# SDRAM.net
KiCad netlist of a schematic drawn in Altium Designer
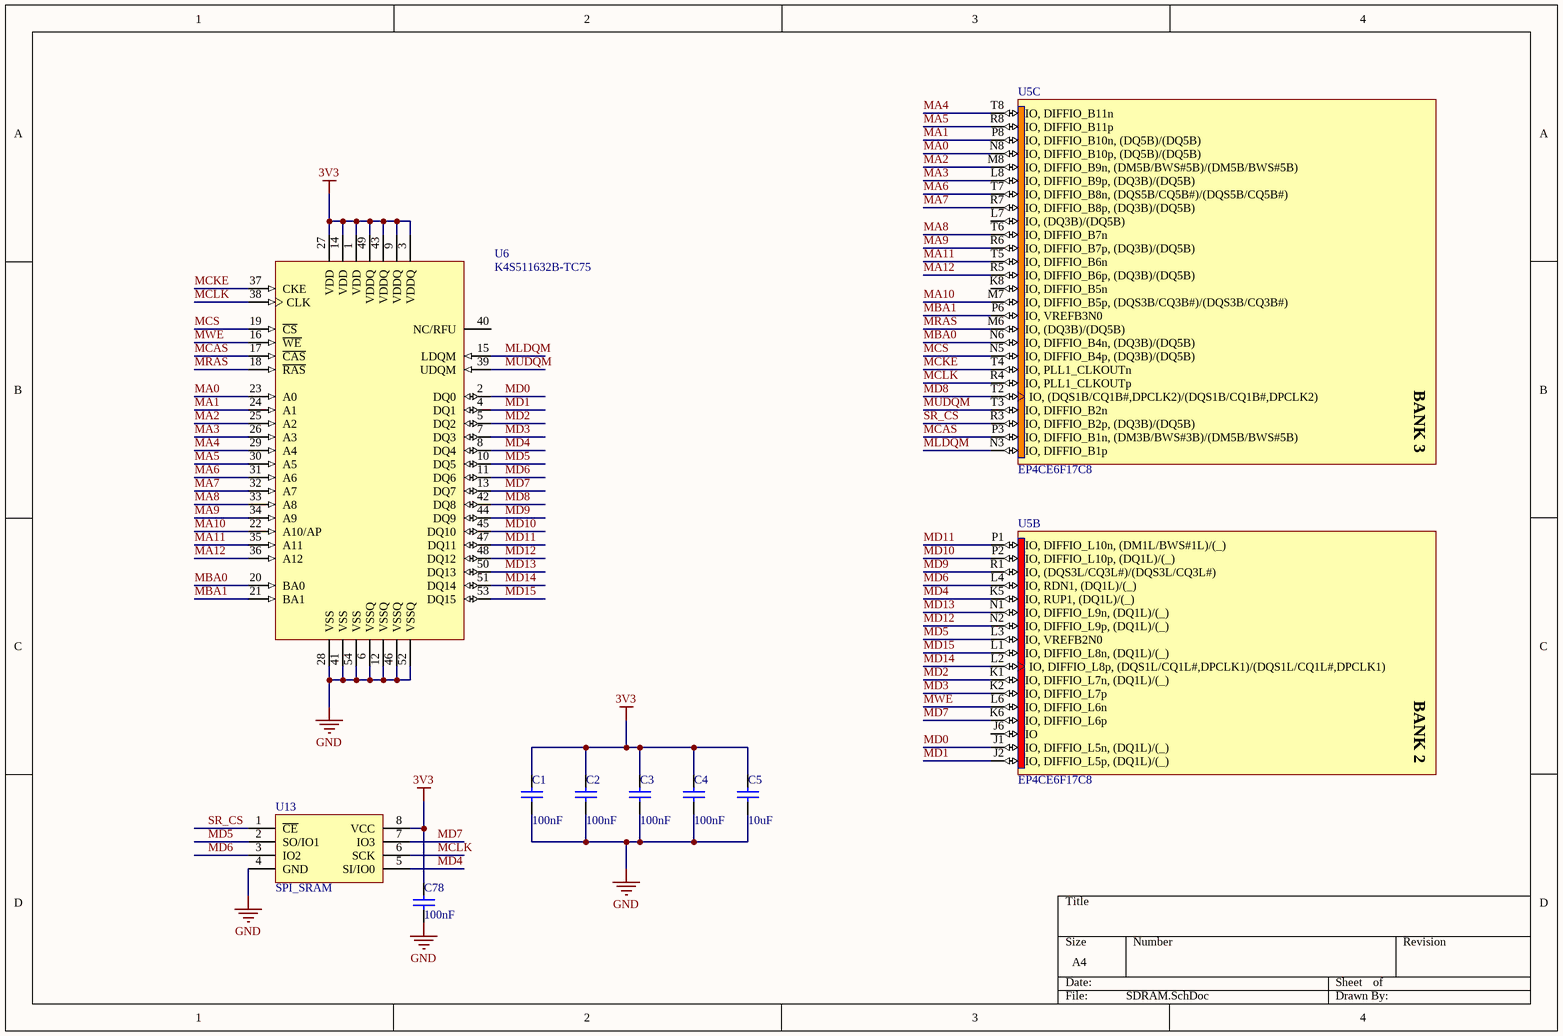
[diagram p0: SDRAM.SchDoc]

(export (version "E")
  (design (tool "Eeschema 10.0.6"))
  (components
    (comp (ref "C1")
      (value "100nF")
      (footprint "C0603")
      (description "Capacitor")
      (fields (field (name "PUBLISHER") "Altium Limited"))
      (libsource (lib "Miscellaneous Devices") (part "Cap"))
    )
    (comp (ref "C2")
      (value "100nF")
      (footprint "C0603")
      (description "Capacitor")
      (fields (field (name "PUBLISHER") "Altium Limited"))
      (libsource (lib "Miscellaneous Devices") (part "Cap"))
    )
    (comp (ref "C3")
      (value "100nF")
      (footprint "C0603")
      (description "Capacitor")
      (fields (field (name "PUBLISHER") "Altium Limited"))
      (libsource (lib "Miscellaneous Devices") (part "Cap"))
    )
    (comp (ref "C4")
      (value "100nF")
      (footprint "C0603")
      (description "Capacitor")
      (fields (field (name "PUBLISHER") "Altium Limited"))
      (libsource (lib "Miscellaneous Devices") (part "Cap"))
    )
    (comp (ref "C5")
      (value "10uF")
      (footprint "C1206")
      (description "Capacitor")
      (fields (field (name "PUBLISHER") "Altium Limited"))
      (libsource (lib "Miscellaneous Devices") (part "Cap"))
    )
    (comp (ref "C78")
      (value "100nF")
      (footprint "C0603")
      (description "Capacitor")
      (fields (field (name "PUBLISHER") "Altium Limited"))
      (libsource (lib "Miscellaneous Devices") (part "Cap"))
    )
    (comp (ref "U5")
      (value "EP4CE6F17C8")
      (footprint "FBGA256")
      (fields (field (name "PUBLISHER") "Altium Limited"))
      (libsource (lib "Altera Cyclone IV E") (part "EP4CE6F17C8"))
    )
    (comp (ref "U6")
      (value "K4S511632B-TC75")
      (footprint "54_TSOP2_400AF_N")
      (description "512Mb Synchronous High Data Rate DRAM, 8Mb x 16Bit x 4 Banks, 54-Pin TSOP")
      (fields (field (name "PUBLISHER") "Altium Limited"))
      (libsource (lib "Samsung Memory Dynamic RAM") (part "K4S511632B-TC75"))
    )
    (comp (ref "U13") (value "SPI_SRAM") (footprint "sop-8_n") (libsource (lib "ssmaster_1") (part "SPIMEM")))
  )
  (nets
    (net (code "1") (name "/MA0") (class "Default")
      (node (ref "U5") (pin "N8") (pinfunction "IO,_DIFFIO_B10p,_(DQ5B)/(DQ5B)_N8") (pintype "bidirectional"))
      (node (ref "U6") (pin "23") (pinfunction "A0_23") (pintype "input"))
    )
    (net (code "2") (name "/MA1") (class "Default")
      (node (ref "U5") (pin "P8") (pinfunction "IO,_DIFFIO_B10n,_(DQ5B)/(DQ5B)_P8") (pintype "bidirectional"))
      (node (ref "U6") (pin "24") (pinfunction "A1_24") (pintype "input"))
    )
    (net (code "3") (name "/MA2") (class "Default")
      (node (ref "U5") (pin "M8") (pinfunction "IO,_DIFFIO_B9n,_(DM5B/BWS#5B)/(DM5B/BWS#5B)_M8") (pintype "bidirectional"))
      (node (ref "U6") (pin "25") (pinfunction "A2_25") (pintype "input"))
    )
    (net (code "4") (name "/MA3") (class "Default")
      (node (ref "U5") (pin "L8") (pinfunction "IO,_DIFFIO_B9p,_(DQ3B)/(DQ5B)_L8") (pintype "bidirectional"))
      (node (ref "U6") (pin "26") (pinfunction "A3_26") (pintype "input"))
    )
    (net (code "5") (name "/MA4") (class "Default")
      (node (ref "U5") (pin "T8") (pinfunction "IO,_DIFFIO_B11n_T8") (pintype "bidirectional"))
      (node (ref "U6") (pin "29") (pinfunction "A4_29") (pintype "input"))
    )
    (net (code "6") (name "/MA5") (class "Default")
      (node (ref "U5") (pin "R8") (pinfunction "IO,_DIFFIO_B11p_R8") (pintype "bidirectional"))
      (node (ref "U6") (pin "30") (pinfunction "A5_30") (pintype "input"))
    )
    (net (code "7") (name "/MA6") (class "Default")
      (node (ref "U5") (pin "T7") (pinfunction "IO,_DIFFIO_B8n,_(DQS5B/CQ5B#)/(DQS5B/CQ5B#)_T7") (pintype "bidirectional"))
      (node (ref "U6") (pin "31") (pinfunction "A6_31") (pintype "input"))
    )
    (net (code "8") (name "/MA7") (class "Default")
      (node (ref "U5") (pin "R7") (pinfunction "IO,_DIFFIO_B8p,_(DQ3B)/(DQ5B)_R7") (pintype "bidirectional"))
      (node (ref "U6") (pin "32") (pinfunction "A7_32") (pintype "input"))
    )
    (net (code "9") (name "/MA8") (class "Default")
      (node (ref "U5") (pin "T6") (pinfunction "IO,_DIFFIO_B7n_T6") (pintype "bidirectional"))
      (node (ref "U6") (pin "33") (pinfunction "A8_33") (pintype "input"))
    )
    (net (code "10") (name "/MA9") (class "Default")
      (node (ref "U5") (pin "R6") (pinfunction "IO,_DIFFIO_B7p,_(DQ3B)/(DQ5B)_R6") (pintype "bidirectional"))
      (node (ref "U6") (pin "34") (pinfunction "A9_34") (pintype "input"))
    )
    (net (code "11") (name "/MA10") (class "Default")
      (node (ref "U5") (pin "M7") (pinfunction "IO,_DIFFIO_B5p,_(DQS3B/CQ3B#)/(DQS3B/CQ3B#)_M7") (pintype "bidirectional"))
      (node (ref "U6") (pin "22") (pinfunction "A10/AP_22") (pintype "input"))
    )
    (net (code "12") (name "/MA11") (class "Default")
      (node (ref "U5") (pin "T5") (pinfunction "IO,_DIFFIO_B6n_T5") (pintype "bidirectional"))
      (node (ref "U6") (pin "35") (pinfunction "A11_35") (pintype "input"))
    )
    (net (code "13") (name "/MA12") (class "Default")
      (node (ref "U5") (pin "R5") (pinfunction "IO,_DIFFIO_B6p,_(DQ3B)/(DQ5B)_R5") (pintype "bidirectional"))
      (node (ref "U6") (pin "36") (pinfunction "A12_36") (pintype "input"))
    )
    (net (code "14") (name "/MBA0") (class "Default")
      (node (ref "U5") (pin "N6") (pinfunction "IO,_DIFFIO_B4n,_(DQ3B)/(DQ5B)_N6") (pintype "bidirectional"))
      (node (ref "U6") (pin "20") (pinfunction "BA0_20") (pintype "input"))
    )
    (net (code "15") (name "/MBA1") (class "Default")
      (node (ref "U5") (pin "P6") (pinfunction "IO,_VREFB3N0_P6") (pintype "bidirectional"))
      (node (ref "U6") (pin "21") (pinfunction "BA1_21") (pintype "input"))
    )
    (net (code "16") (name "/MCAS") (class "Default")
      (node (ref "U5") (pin "P3") (pinfunction "IO,_DIFFIO_B1n,_(DM3B/BWS#3B)/(DM5B/BWS#5B)_P3") (pintype "bidirectional"))
      (node (ref "U6") (pin "17") (pinfunction "~{CAS}_17") (pintype "input"))
    )
    (net (code "17") (name "/MCKE") (class "Default")
      (node (ref "U5") (pin "T4") (pinfunction "IO,_PLL1_CLKOUTn_T4") (pintype "bidirectional"))
      (node (ref "U6") (pin "37") (pinfunction "CKE_37") (pintype "input"))
    )
    (net (code "18") (name "/MCLK") (class "Default")
      (node (ref "U13") (pin "6") (pinfunction "SCK_6") (pintype "passive"))
      (node (ref "U5") (pin "R4") (pinfunction "IO,_PLL1_CLKOUTp_R4") (pintype "bidirectional"))
      (node (ref "U6") (pin "38") (pinfunction "CLK_38") (pintype "input"))
    )
    (net (code "19") (name "/MCS") (class "Default")
      (node (ref "U5") (pin "N5") (pinfunction "IO,_DIFFIO_B4p,_(DQ3B)/(DQ5B)_N5") (pintype "bidirectional"))
      (node (ref "U6") (pin "19") (pinfunction "~{CS}_19") (pintype "input"))
    )
    (net (code "20") (name "/MD0") (class "Default")
      (node (ref "U5") (pin "J1") (pinfunction "IO,_DIFFIO_L5n,_(DQ1L)/(_)_J1") (pintype "bidirectional"))
      (node (ref "U6") (pin "2") (pinfunction "DQ0_2") (pintype "bidirectional"))
    )
    (net (code "21") (name "/MD1") (class "Default")
      (node (ref "U5") (pin "J2") (pinfunction "IO,_DIFFIO_L5p,_(DQ1L)/(_)_J2") (pintype "bidirectional"))
      (node (ref "U6") (pin "4") (pinfunction "DQ1_4") (pintype "bidirectional"))
    )
    (net (code "22") (name "/MD2") (class "Default")
      (node (ref "U5") (pin "K1") (pinfunction "IO,_DIFFIO_L7n,_(DQ1L)/(_)_K1") (pintype "bidirectional"))
      (node (ref "U6") (pin "5") (pinfunction "DQ2_5") (pintype "bidirectional"))
    )
    (net (code "23") (name "/MD3") (class "Default")
      (node (ref "U5") (pin "K2") (pinfunction "IO,_DIFFIO_L7p_K2") (pintype "bidirectional"))
      (node (ref "U6") (pin "7") (pinfunction "DQ3_7") (pintype "bidirectional"))
    )
    (net (code "24") (name "/MD4") (class "Default")
      (node (ref "U13") (pin "5") (pinfunction "SI/IO0_5") (pintype "passive"))
      (node (ref "U5") (pin "K5") (pinfunction "IO,_RUP1,_(DQ1L)/(_)_K5") (pintype "bidirectional"))
      (node (ref "U6") (pin "8") (pinfunction "DQ4_8") (pintype "bidirectional"))
    )
    (net (code "25") (name "/MD5") (class "Default")
      (node (ref "U13") (pin "2") (pinfunction "SO/IO1_2") (pintype "passive"))
      (node (ref "U5") (pin "L3") (pinfunction "IO,_VREFB2N0_L3") (pintype "bidirectional"))
      (node (ref "U6") (pin "10") (pinfunction "DQ5_10") (pintype "bidirectional"))
    )
    (net (code "26") (name "/MD6") (class "Default")
      (node (ref "U13") (pin "3") (pinfunction "IO2_3") (pintype "passive"))
      (node (ref "U5") (pin "L4") (pinfunction "IO,_RDN1,_(DQ1L)/(_)_L4") (pintype "bidirectional"))
      (node (ref "U6") (pin "11") (pinfunction "DQ6_11") (pintype "bidirectional"))
    )
    (net (code "27") (name "/MD7") (class "Default")
      (node (ref "U13") (pin "7") (pinfunction "IO3_7") (pintype "passive"))
      (node (ref "U5") (pin "K6") (pinfunction "IO,_DIFFIO_L6p_K6") (pintype "bidirectional"))
      (node (ref "U6") (pin "13") (pinfunction "DQ7_13") (pintype "bidirectional"))
    )
    (net (code "28") (name "/MD8") (class "Default")
      (node (ref "U5") (pin "T2") (pinfunction "IO,_(DQS1B/CQ1B#,DPCLK2)/(DQS1B/CQ1B#,DPCLK2)_T2") (pintype "bidirectional"))
      (node (ref "U6") (pin "42") (pinfunction "DQ8_42") (pintype "bidirectional"))
    )
    (net (code "29") (name "/MD9") (class "Default")
      (node (ref "U5") (pin "R1") (pinfunction "IO,_(DQS3L/CQ3L#)/(DQS3L/CQ3L#)_R1") (pintype "bidirectional"))
      (node (ref "U6") (pin "44") (pinfunction "DQ9_44") (pintype "bidirectional"))
    )
    (net (code "30") (name "/MD10") (class "Default")
      (node (ref "U5") (pin "P2") (pinfunction "IO,_DIFFIO_L10p,_(DQ1L)/(_)_P2") (pintype "bidirectional"))
      (node (ref "U6") (pin "45") (pinfunction "DQ10_45") (pintype "bidirectional"))
    )
    (net (code "31") (name "/MD11") (class "Default")
      (node (ref "U5") (pin "P1") (pinfunction "IO,_DIFFIO_L10n,_(DM1L/BWS#1L)/(_)_P1") (pintype "bidirectional"))
      (node (ref "U6") (pin "47") (pinfunction "DQ11_47") (pintype "bidirectional"))
    )
    (net (code "32") (name "/MD12") (class "Default")
      (node (ref "U5") (pin "N2") (pinfunction "IO,_DIFFIO_L9p,_(DQ1L)/(_)_N2") (pintype "bidirectional"))
      (node (ref "U6") (pin "48") (pinfunction "DQ12_48") (pintype "bidirectional"))
    )
    (net (code "33") (name "/MD13") (class "Default")
      (node (ref "U5") (pin "N1") (pinfunction "IO,_DIFFIO_L9n,_(DQ1L)/(_)_N1") (pintype "bidirectional"))
      (node (ref "U6") (pin "50") (pinfunction "DQ13_50") (pintype "bidirectional"))
    )
    (net (code "34") (name "/MD14") (class "Default")
      (node (ref "U5") (pin "L2") (pinfunction "IO,_DIFFIO_L8p,_(DQS1L/CQ1L#,DPCLK1)/(DQS1L/CQ1L#,DPCLK1)_L2") (pintype "bidirectional"))
      (node (ref "U6") (pin "51") (pinfunction "DQ14_51") (pintype "bidirectional"))
    )
    (net (code "35") (name "/MD15") (class "Default")
      (node (ref "U5") (pin "L1") (pinfunction "IO,_DIFFIO_L8n,_(DQ1L)/(_)_L1") (pintype "bidirectional"))
      (node (ref "U6") (pin "53") (pinfunction "DQ15_53") (pintype "bidirectional"))
    )
    (net (code "36") (name "/MLDQM") (class "Default")
      (node (ref "U5") (pin "N3") (pinfunction "IO,_DIFFIO_B1p_N3") (pintype "bidirectional"))
      (node (ref "U6") (pin "15") (pinfunction "LDQM_15") (pintype "input"))
    )
    (net (code "37") (name "/MRAS") (class "Default")
      (node (ref "U5") (pin "M6") (pinfunction "IO,_(DQ3B)/(DQ5B)_M6") (pintype "bidirectional"))
      (node (ref "U6") (pin "18") (pinfunction "~{RAS}_18") (pintype "input"))
    )
    (net (code "38") (name "/MUDQM") (class "Default")
      (node (ref "U5") (pin "T3") (pinfunction "IO,_DIFFIO_B2n_T3") (pintype "bidirectional"))
      (node (ref "U6") (pin "39") (pinfunction "UDQM_39") (pintype "input"))
    )
    (net (code "39") (name "/MWE") (class "Default")
      (node (ref "U5") (pin "L6") (pinfunction "IO,_DIFFIO_L6n_L6") (pintype "bidirectional"))
      (node (ref "U6") (pin "16") (pinfunction "~{WE}_16") (pintype "input"))
    )
    (net (code "40") (name "/SR_CS") (class "Default")
      (node (ref "U13") (pin "1") (pinfunction "~{CE}_1") (pintype "passive"))
      (node (ref "U5") (pin "R3") (pinfunction "IO,_DIFFIO_B2p,_(DQ3B)/(DQ5B)_R3") (pintype "bidirectional"))
    )
    (net (code "41") (name "3V3") (class "Default")
      (node (ref "C1") (pin "2") (pinfunction "2_2") (pintype "passive"))
      (node (ref "C2") (pin "2") (pinfunction "2_2") (pintype "passive"))
      (node (ref "C3") (pin "2") (pinfunction "2_2") (pintype "passive"))
      (node (ref "C4") (pin "2") (pinfunction "2_2") (pintype "passive"))
      (node (ref "C5") (pin "1") (pinfunction "1_1") (pintype "passive"))
      (node (ref "C78") (pin "2") (pinfunction "2_2") (pintype "passive"))
      (node (ref "U13") (pin "8") (pinfunction "VCC_8") (pintype "power_in"))
      (node (ref "U6") (pin "1") (pinfunction "VDD_1") (pintype "power_in"))
      (node (ref "U6") (pin "14") (pinfunction "VDD_14") (pintype "power_in"))
      (node (ref "U6") (pin "27") (pinfunction "VDD_27") (pintype "power_in"))
      (node (ref "U6") (pin "3") (pinfunction "VDDQ_3") (pintype "power_in"))
      (node (ref "U6") (pin "43") (pinfunction "VDDQ_43") (pintype "power_in"))
      (node (ref "U6") (pin "49") (pinfunction "VDDQ_49") (pintype "power_in"))
      (node (ref "U6") (pin "9") (pinfunction "VDDQ_9") (pintype "power_in"))
    )
    (net (code "42") (name "GND") (class "Default")
      (node (ref "C1") (pin "1") (pinfunction "1_1") (pintype "passive"))
      (node (ref "C2") (pin "1") (pinfunction "1_1") (pintype "passive"))
      (node (ref "C3") (pin "1") (pinfunction "1_1") (pintype "passive"))
      (node (ref "C4") (pin "1") (pinfunction "1_1") (pintype "passive"))
      (node (ref "C5") (pin "2") (pinfunction "2_2") (pintype "passive"))
      (node (ref "C78") (pin "1") (pinfunction "1_1") (pintype "passive"))
      (node (ref "U13") (pin "4") (pinfunction "GND_4") (pintype "power_in"))
      (node (ref "U6") (pin "12") (pinfunction "VSSQ_12") (pintype "power_in"))
      (node (ref "U6") (pin "28") (pinfunction "VSS_28") (pintype "power_in"))
      (node (ref "U6") (pin "41") (pinfunction "VSS_41") (pintype "power_in"))
      (node (ref "U6") (pin "46") (pinfunction "VSSQ_46") (pintype "power_in"))
      (node (ref "U6") (pin "52") (pinfunction "VSSQ_52") (pintype "power_in"))
      (node (ref "U6") (pin "54") (pinfunction "VSS_54") (pintype "power_in"))
      (node (ref "U6") (pin "6") (pinfunction "VSSQ_6") (pintype "power_in"))
    )
    (net (code "43") (name "unconnected-(U5B-IO-PadJ6)") (class "Default")
      (node (ref "U5") (pin "J6") (pinfunction "IO_J6") (pintype "bidirectional"))
    )
    (net (code "44") (name "unconnected-(U5C-IO,_(DQ3B){slash}(DQ5B)-PadL7)") (class "Default")
      (node (ref "U5") (pin "L7") (pinfunction "IO,_(DQ3B)/(DQ5B)_L7") (pintype "bidirectional"))
    )
    (net (code "45") (name "unconnected-(U5C-IO,_DIFFIO_B5n-PadK8)") (class "Default")
      (node (ref "U5") (pin "K8") (pinfunction "IO,_DIFFIO_B5n_K8") (pintype "bidirectional"))
    )
    (net (code "46") (name "unconnected-(U6-NC{slash}RFU-Pad40)") (class "Default")
      (node (ref "U6") (pin "40") (pinfunction "NC/RFU_40") (pintype "passive"))
    )
  )
)
